# LLaveAnalogica.net
KiCad netlist of a schematic drawn in Altium Designer
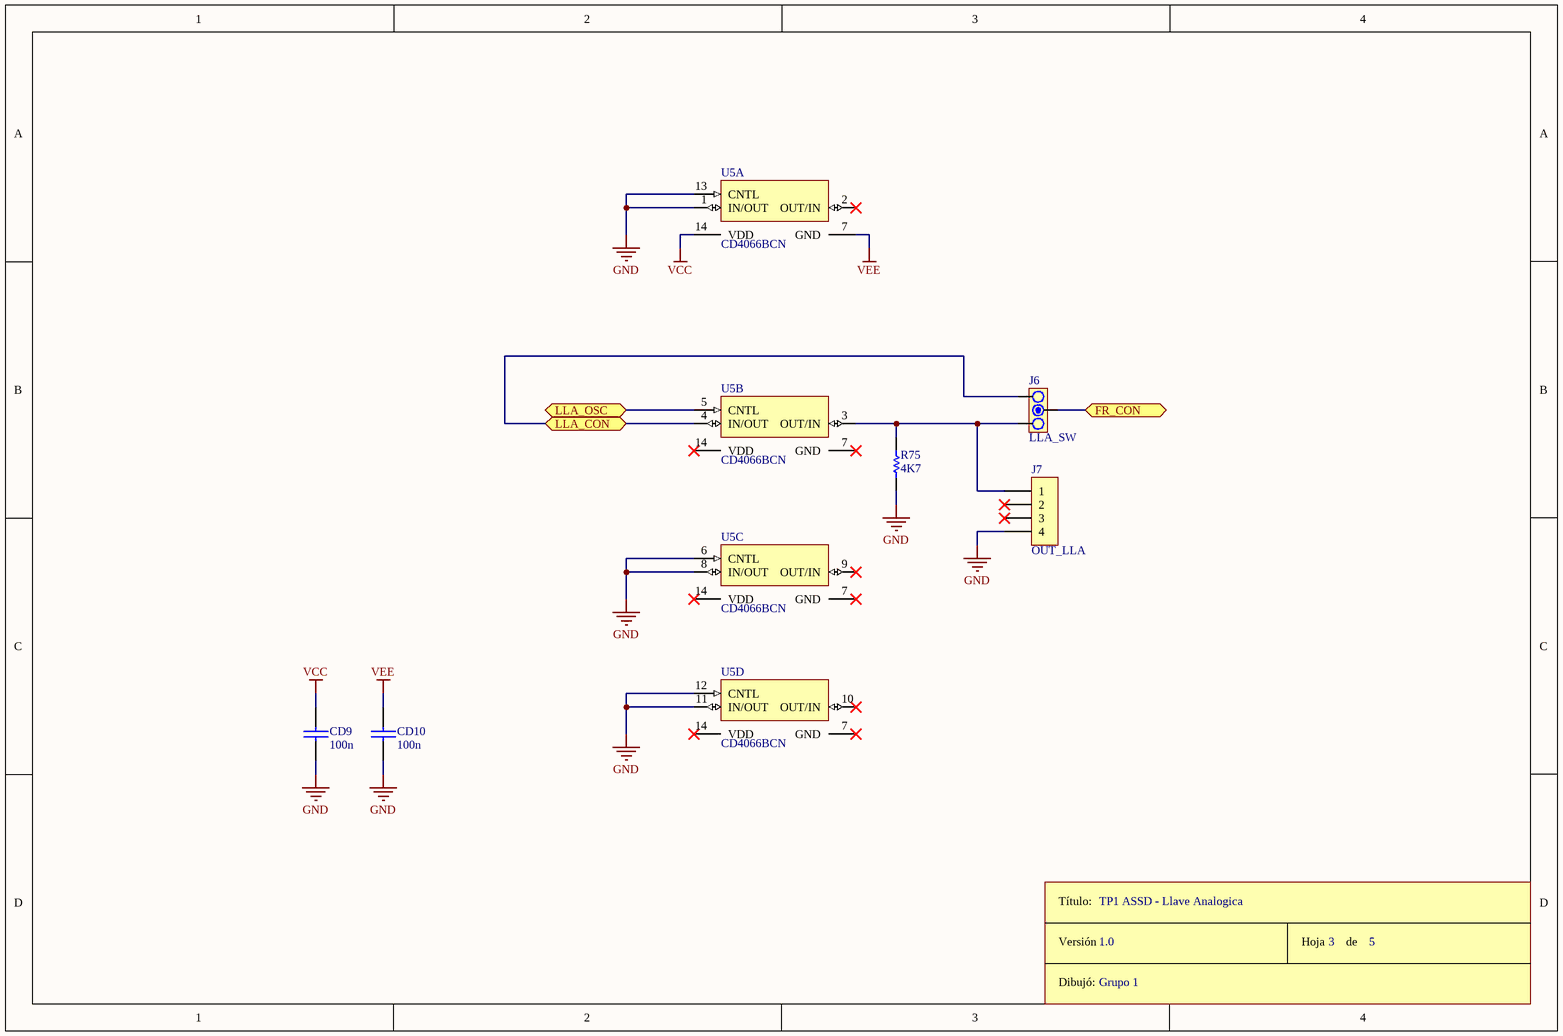
[diagram p0: LLaveAnalogica.SchDoc]

(export (version "E")
  (design (tool "Eeschema 10.0.6"))
  (components
    (comp (ref "CD9") (value "100n") (footprint "CAP100") (libsource (lib "LIBEBAL") (part "CAP")))
    (comp (ref "CD10") (value "100n") (footprint "CAP100") (libsource (lib "LIBEBAL") (part "CAP")))
    (comp (ref "J6") (value "LLA_SW") (footprint "JUMPER3") (libsource (lib "LIBEBAL") (part "JUMPER3")))
    (comp (ref "J7") (value "OUT_LLA") (footprint "SIP4") (libsource (lib "LIBEBAL") (part "CON4")))
    (comp (ref "R75") (value "4K7") (footprint "RES400") (libsource (lib "LIBEBAL") (part "RES")))
    (comp (ref "ROT3") (value "Rótulo") (libsource (lib "LIB PIO IX") (part "Rótulo")))
    (comp (ref "U5")
      (value "CD4066BCN")
      (footprint "N14A")
      (description "Quad Bilateral Switch")
      (fields (field (name "PUBLISHER") "Altium Limited"))
      (libsource (lib "FSC Logic Switch") (part "CD4066BCN"))
    )
  )
  (nets
    (net (code "1") (name "/FR_CON") (class "Default")
      (node (ref "J6") (pin "2") (pinfunction "2_2") (pintype "passive"))
    )
    (net (code "2") (name "/LLA_CON") (class "Default")
      (node (ref "J6") (pin "3") (pinfunction "3_3") (pintype "passive"))
      (node (ref "U5") (pin "4") (pinfunction "IN/OUT_4") (pintype "bidirectional"))
    )
    (net (code "3") (name "/LLA_OSC") (class "Default")
      (node (ref "U5") (pin "5") (pinfunction "CNTL_5") (pintype "input"))
    )
    (net (code "4") (name "GND") (class "Default")
      (node (ref "CD10") (pin "1") (pinfunction "1_1") (pintype "passive"))
      (node (ref "CD10") (pin "2") (pinfunction "2_2") (pintype "passive"))
      (node (ref "CD9") (pin "2") (pinfunction "2_2") (pintype "passive"))
      (node (ref "J7") (pin "4") (pinfunction "4_4") (pintype "passive"))
      (node (ref "R75") (pin "1") (pinfunction "1_1") (pintype "passive"))
      (node (ref "U5") (pin "1") (pinfunction "IN/OUT_1") (pintype "bidirectional"))
      (node (ref "U5") (pin "11") (pinfunction "IN/OUT_11") (pintype "bidirectional"))
      (node (ref "U5") (pin "12") (pinfunction "CNTL_12") (pintype "input"))
      (node (ref "U5") (pin "13") (pinfunction "CNTL_13") (pintype "input"))
      (node (ref "U5") (pin "6") (pinfunction "CNTL_6") (pintype "input"))
      (node (ref "U5") (pin "7") (pinfunction "GND_7") (pintype "power_in"))
      (node (ref "U5") (pin "8") (pinfunction "IN/OUT_8") (pintype "bidirectional"))
    )
    (net (code "5") (name "Net-(U5B-OUT{slash}IN)") (class "Default")
      (node (ref "J6") (pin "1") (pinfunction "1_1") (pintype "passive"))
      (node (ref "J7") (pin "1") (pinfunction "1_1") (pintype "passive"))
      (node (ref "R75") (pin "2") (pinfunction "2_2") (pintype "passive"))
      (node (ref "U5") (pin "3") (pinfunction "OUT/IN_3") (pintype "bidirectional"))
    )
    (net (code "6") (name "VCC") (class "Default")
      (node (ref "CD9") (pin "1") (pinfunction "1_1") (pintype "passive"))
      (node (ref "U5") (pin "14") (pinfunction "VDD_14") (pintype "power_in"))
    )
    (net (code "7") (name "unconnected-(J7-Pad2)") (class "Default")
      (node (ref "J7") (pin "2") (pinfunction "2_2") (pintype "passive+no_connect"))
    )
    (net (code "8") (name "unconnected-(J7-Pad3)") (class "Default")
      (node (ref "J7") (pin "3") (pinfunction "3_3") (pintype "passive+no_connect"))
    )
    (net (code "9") (name "unconnected-(U5A-OUT{slash}IN-Pad2)") (class "Default")
      (node (ref "U5") (pin "2") (pinfunction "OUT/IN_2") (pintype "bidirectional+no_connect"))
    )
    (net (code "10") (name "unconnected-(U5C-OUT{slash}IN-Pad9)") (class "Default")
      (node (ref "U5") (pin "9") (pinfunction "OUT/IN_9") (pintype "bidirectional+no_connect"))
    )
    (net (code "11") (name "unconnected-(U5D-OUT{slash}IN-Pad10)") (class "Default")
      (node (ref "U5") (pin "10") (pinfunction "OUT/IN_10") (pintype "bidirectional+no_connect"))
    )
  )
)
